# four_axis_part2.net
KiCad netlist of a schematic drawn in Altium Designer
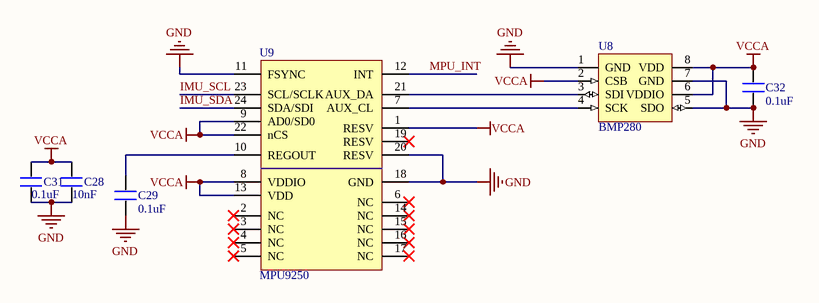
[diagram p0: four_axis_part2.SchDoc]

(export (version "E")
  (design (tool "Eeschema 10.0.6"))
  (components
    (comp (ref "C28") (value "10nF") (footprint "0603P") (libsource (lib "MiniFly ") (part "C")))
    (comp (ref "C29") (value "0.1uF") (footprint "0603P") (libsource (lib "MiniFly ") (part "C")))
    (comp (ref "C31") (value "0.1uF") (footprint "0603P") (libsource (lib "MiniFly ") (part "C")))
    (comp (ref "C32") (value "0.1uF") (footprint "0603P") (libsource (lib "MiniFly ") (part "C")))
    (comp (ref "U8") (value "BMP280") (footprint "LGA-8") (libsource (lib "MiniFly ") (part "BMP280")))
    (comp (ref "U9") (value "MPU9250") (footprint "QFN24-0.4") (libsource (lib "MiniFly ") (part "MPU9250")))
  )
  (nets
    (net (code "1") (name "/IMU_SCL") (class "Default")
      (node (ref "U9") (pin "23") (pinfunction "SCL/SCLK_23") (pintype "passive"))
    )
    (net (code "2") (name "/IMU_SDA") (class "Default")
      (node (ref "U9") (pin "24") (pinfunction "SDA/SDI_24") (pintype "passive"))
    )
    (net (code "3") (name "/MPU_INT") (class "Default")
      (node (ref "U9") (pin "12") (pinfunction "INT_12") (pintype "passive"))
    )
    (net (code "4") (name "GND") (class "Default")
      (node (ref "C28") (pin "1") (pintype "passive"))
      (node (ref "C29") (pin "1") (pintype "passive"))
      (node (ref "C31") (pin "1") (pintype "passive"))
      (node (ref "C32") (pin "1") (pintype "passive"))
      (node (ref "U8") (pin "1") (pinfunction "GND_1") (pintype "passive"))
      (node (ref "U8") (pin "5") (pinfunction "SDO_5") (pintype "bidirectional"))
      (node (ref "U8") (pin "7") (pinfunction "GND_7") (pintype "power_in"))
      (node (ref "U9") (pin "11") (pinfunction "FSYNC_11") (pintype "passive"))
      (node (ref "U9") (pin "18") (pinfunction "GND_18") (pintype "passive"))
      (node (ref "U9") (pin "20") (pinfunction "RESV_20") (pintype "passive"))
    )
    (net (code "5") (name "Net-(U8-SCK)") (class "Default")
      (node (ref "U8") (pin "4") (pinfunction "SCK_4") (pintype "input"))
      (node (ref "U9") (pin "7") (pinfunction "AUX_CL_7") (pintype "passive"))
    )
    (net (code "6") (name "Net-(U8-SDI)") (class "Default")
      (node (ref "U8") (pin "3") (pinfunction "SDI_3") (pintype "bidirectional"))
      (node (ref "U9") (pin "21") (pinfunction "AUX_DA_21") (pintype "passive"))
    )
    (net (code "7") (name "Net-(U9-REGOUT)") (class "Default")
      (node (ref "C29") (pin "2") (pintype "passive"))
      (node (ref "U9") (pin "10") (pinfunction "REGOUT_10") (pintype "passive"))
    )
    (net (code "8") (name "VCCA") (class "Default")
      (node (ref "C28") (pin "2") (pintype "passive"))
      (node (ref "C31") (pin "2") (pintype "passive"))
      (node (ref "C32") (pin "2") (pintype "passive"))
      (node (ref "U8") (pin "2") (pinfunction "CSB_2") (pintype "input"))
      (node (ref "U8") (pin "6") (pinfunction "VDDIO_6") (pintype "power_in"))
      (node (ref "U8") (pin "8") (pinfunction "VDD_8") (pintype "power_in"))
      (node (ref "U9") (pin "1") (pinfunction "RESV_1") (pintype "passive"))
      (node (ref "U9") (pin "13") (pinfunction "VDD_13") (pintype "passive"))
      (node (ref "U9") (pin "22") (pinfunction "nCS_22") (pintype "passive"))
      (node (ref "U9") (pin "8") (pinfunction "VDDIO_8") (pintype "passive"))
      (node (ref "U9") (pin "9") (pinfunction "AD0/SD0_9") (pintype "passive"))
    )
    (net (code "9") (name "unconnected-(U9-NC-Pad2)") (class "Default")
      (node (ref "U9") (pin "2") (pinfunction "NC_2") (pintype "passive+no_connect"))
    )
    (net (code "10") (name "unconnected-(U9-NC-Pad3)") (class "Default")
      (node (ref "U9") (pin "3") (pinfunction "NC_3") (pintype "passive+no_connect"))
    )
    (net (code "11") (name "unconnected-(U9-NC-Pad4)") (class "Default")
      (node (ref "U9") (pin "4") (pinfunction "NC_4") (pintype "passive+no_connect"))
    )
    (net (code "12") (name "unconnected-(U9-NC-Pad5)") (class "Default")
      (node (ref "U9") (pin "5") (pinfunction "NC_5") (pintype "passive+no_connect"))
    )
    (net (code "13") (name "unconnected-(U9-NC-Pad6)") (class "Default")
      (node (ref "U9") (pin "6") (pinfunction "NC_6") (pintype "passive+no_connect"))
    )
    (net (code "14") (name "unconnected-(U9-NC-Pad14)") (class "Default")
      (node (ref "U9") (pin "14") (pinfunction "NC_14") (pintype "passive+no_connect"))
    )
    (net (code "15") (name "unconnected-(U9-NC-Pad15)") (class "Default")
      (node (ref "U9") (pin "15") (pinfunction "NC_15") (pintype "passive+no_connect"))
    )
    (net (code "16") (name "unconnected-(U9-NC-Pad16)") (class "Default")
      (node (ref "U9") (pin "16") (pinfunction "NC_16") (pintype "passive+no_connect"))
    )
    (net (code "17") (name "unconnected-(U9-NC-Pad17)") (class "Default")
      (node (ref "U9") (pin "17") (pinfunction "NC_17") (pintype "passive+no_connect"))
    )
    (net (code "18") (name "unconnected-(U9-RESV-Pad19)") (class "Default")
      (node (ref "U9") (pin "19") (pinfunction "RESV_19") (pintype "passive+no_connect"))
    )
  )
)
